# Sheet_2.net
KiCad netlist of a schematic drawn in EasyEDA
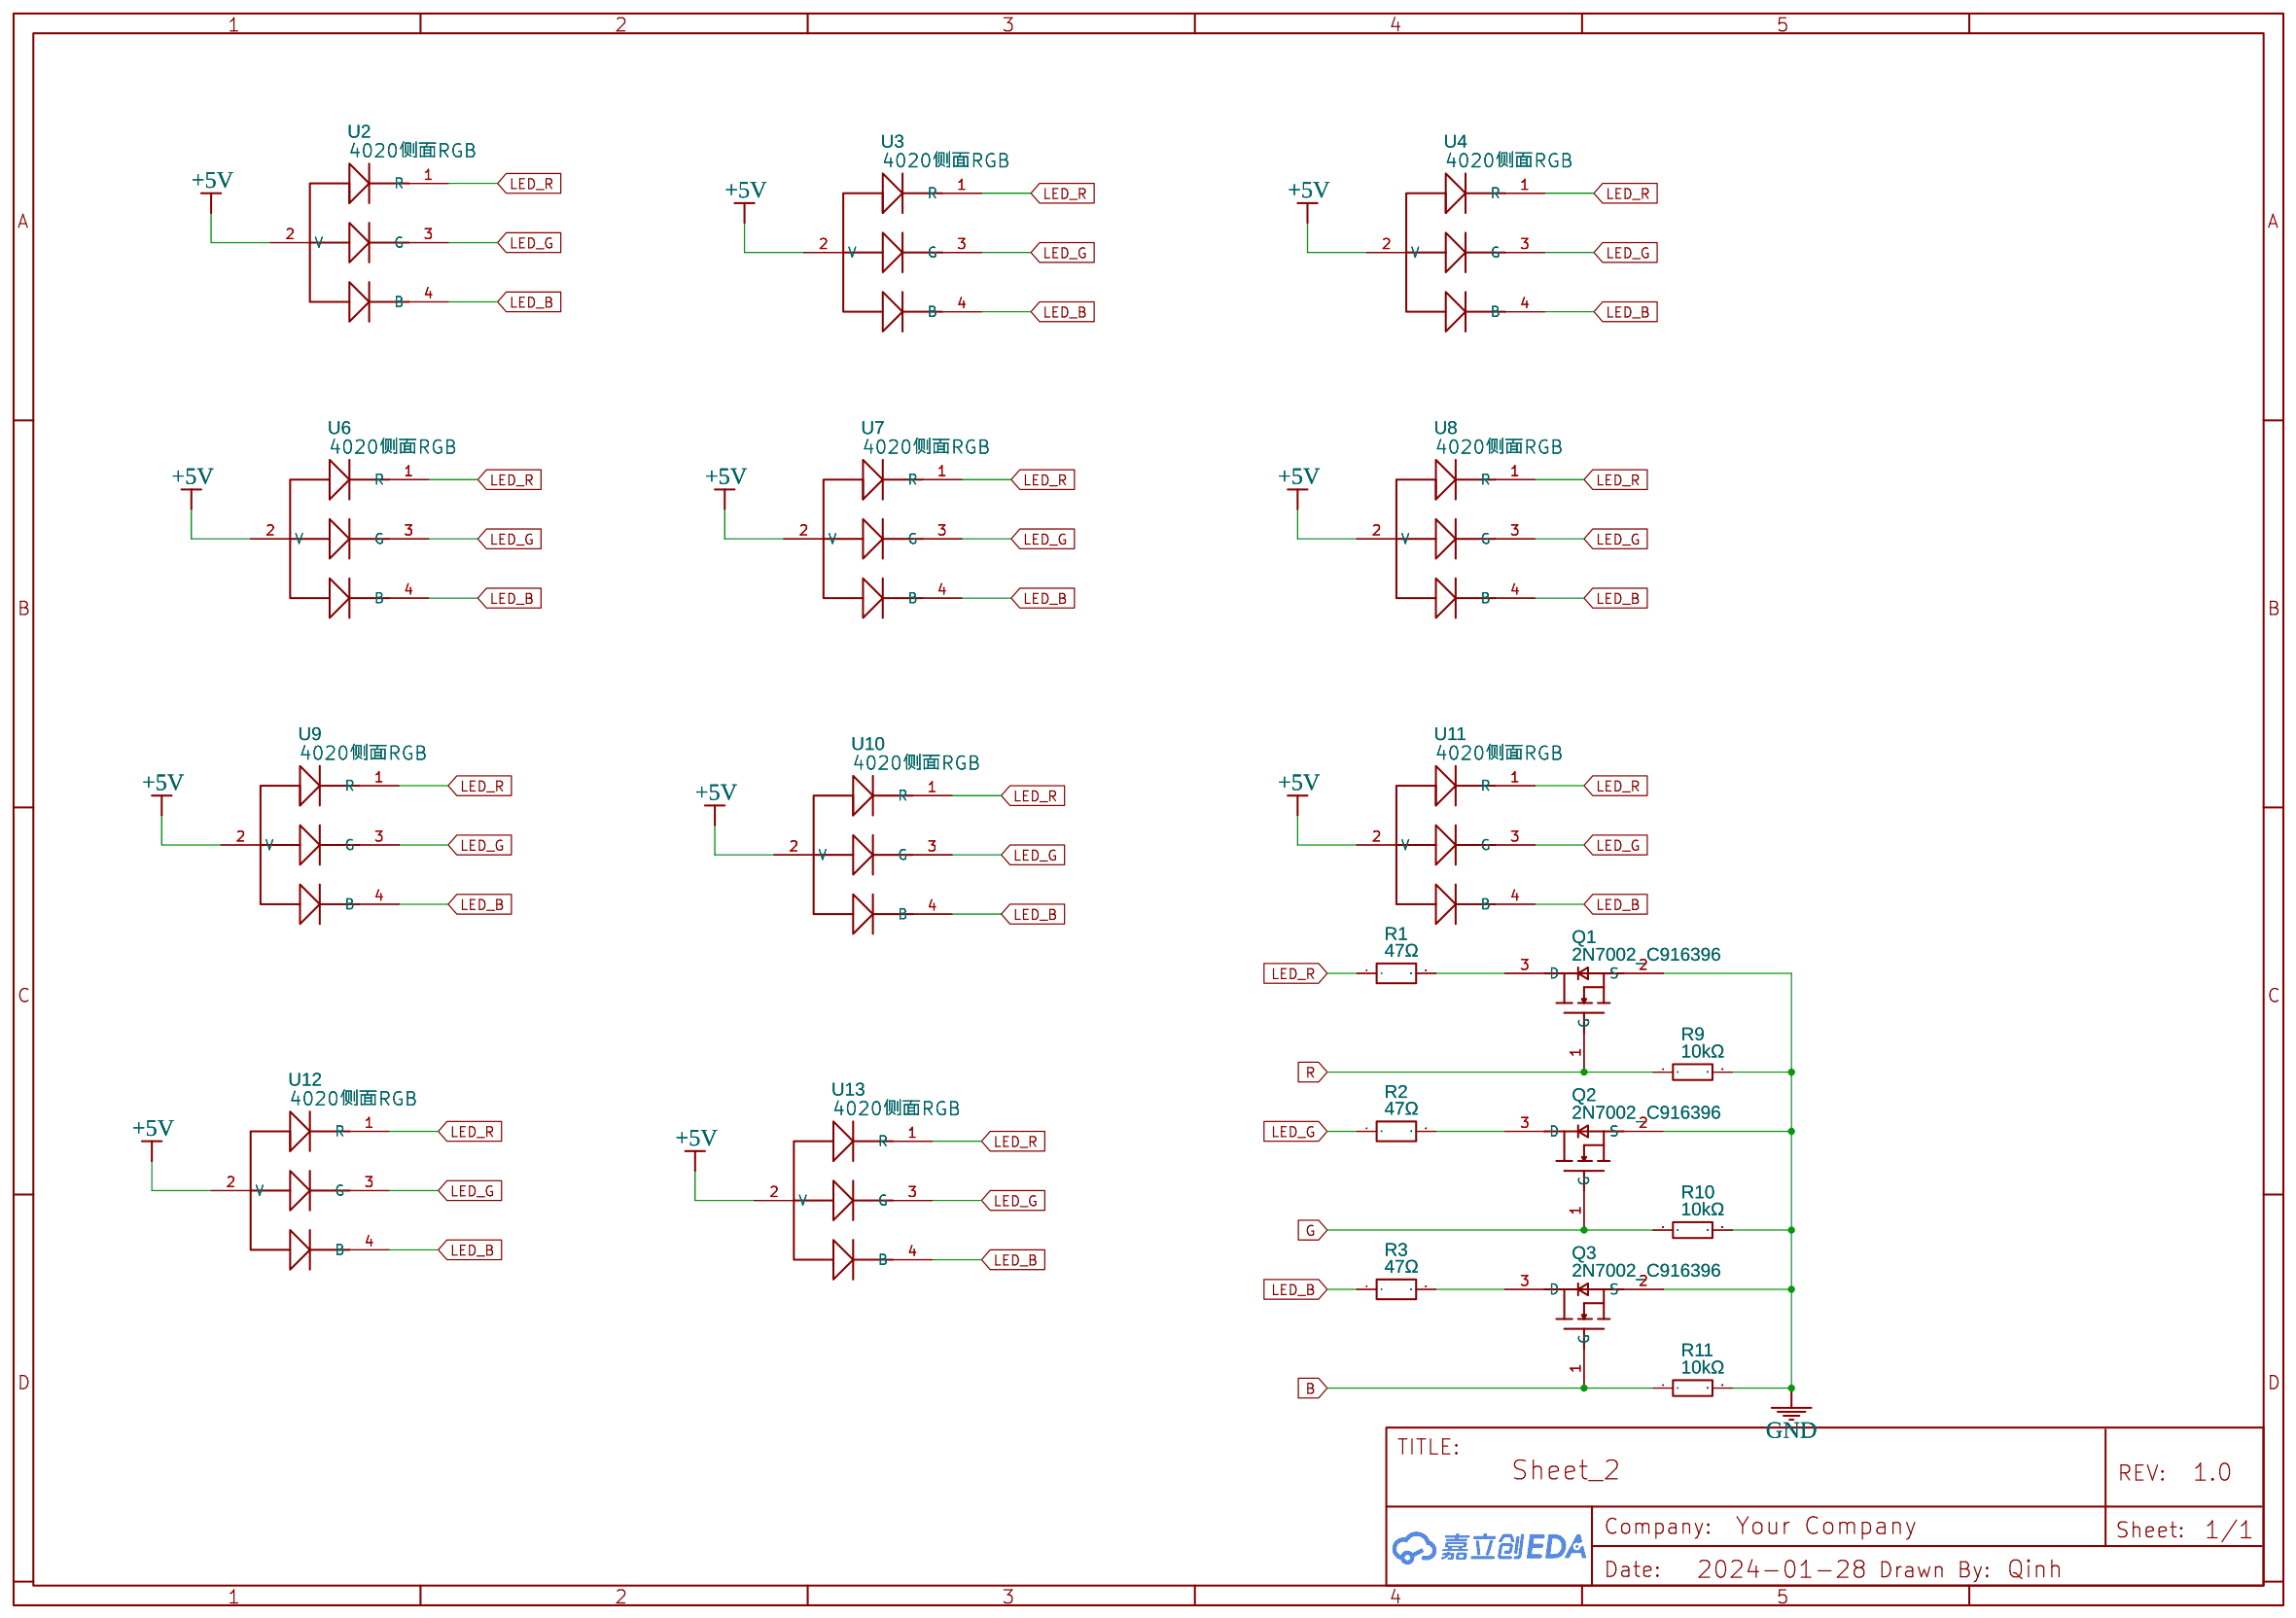
[diagram p0: schematic sheet]

(export (version "E")
  (design (tool "Eeschema 10.0.6"))
  (components
    (comp (ref "Q1")
      (value "2N7002_C916396")
      (fields (field (name "Manufacturer Part") "2N7002") (field (name "Manufacturer") "JSMSEMI(杰盛微)"))
      (libsource (lib "") (part "2N7002_C916396"))
    )
    (comp (ref "Q2")
      (value "2N7002_C916396")
      (fields (field (name "Manufacturer Part") "2N7002") (field (name "Manufacturer") "JSMSEMI(杰盛微)"))
      (libsource (lib "") (part "2N7002_C916396"))
    )
    (comp (ref "Q3")
      (value "2N7002_C916396")
      (fields (field (name "Manufacturer Part") "2N7002") (field (name "Manufacturer") "JSMSEMI(杰盛微)"))
      (libsource (lib "") (part "2N7002_C916396"))
    )
    (comp (ref "R1")
      (value "47Ω")
      (fields
        (field (name "Manufacturer Part") "CRCW060347R0FKEA")
        (field (name "Manufacturer") "VISHAY(威世)")
      )
      (libsource (lib "") (part "CRCW060347R0FKEA"))
    )
    (comp (ref "R2")
      (value "47Ω")
      (fields
        (field (name "Manufacturer Part") "CRCW060347R0FKEA")
        (field (name "Manufacturer") "VISHAY(威世)")
      )
      (libsource (lib "") (part "CRCW060347R0FKEA"))
    )
    (comp (ref "R3")
      (value "47Ω")
      (fields
        (field (name "Manufacturer Part") "CRCW060347R0FKEA")
        (field (name "Manufacturer") "VISHAY(威世)")
      )
      (libsource (lib "") (part "CRCW060347R0FKEA"))
    )
    (comp (ref "R9")
      (value "10kΩ")
      (fields
        (field (name "Manufacturer Part") "0603WAF1002T5E")
        (field (name "Manufacturer") "UNI-ROYAL(厚声)")
      )
      (libsource (lib "") (part "0603WAF1002T5E"))
    )
    (comp (ref "R10")
      (value "10kΩ")
      (fields
        (field (name "Manufacturer Part") "0603WAF1002T5E")
        (field (name "Manufacturer") "UNI-ROYAL(厚声)")
      )
      (libsource (lib "") (part "0603WAF1002T5E"))
    )
    (comp (ref "R11")
      (value "10kΩ")
      (fields
        (field (name "Manufacturer Part") "0603WAF1002T5E")
        (field (name "Manufacturer") "UNI-ROYAL(厚声)")
      )
      (libsource (lib "") (part "0603WAF1002T5E"))
    )
    (comp (ref "U2") (value "4020侧面RGB") (libsource (lib "") (part "4020侧面RGB")))
    (comp (ref "U3") (value "4020侧面RGB") (libsource (lib "") (part "4020侧面RGB")))
    (comp (ref "U4") (value "4020侧面RGB") (libsource (lib "") (part "4020侧面RGB")))
    (comp (ref "U6") (value "4020侧面RGB") (libsource (lib "") (part "4020侧面RGB")))
    (comp (ref "U7") (value "4020侧面RGB") (libsource (lib "") (part "4020侧面RGB")))
    (comp (ref "U8") (value "4020侧面RGB") (libsource (lib "") (part "4020侧面RGB")))
    (comp (ref "U9") (value "4020侧面RGB") (libsource (lib "") (part "4020侧面RGB")))
    (comp (ref "U10") (value "4020侧面RGB") (libsource (lib "") (part "4020侧面RGB")))
    (comp (ref "U11") (value "4020侧面RGB") (libsource (lib "") (part "4020侧面RGB")))
    (comp (ref "U12") (value "4020侧面RGB") (libsource (lib "") (part "4020侧面RGB")))
    (comp (ref "U13") (value "4020侧面RGB") (libsource (lib "") (part "4020侧面RGB")))
  )
  (nets
    (net (code "1") (name "+5V") (class "Default")
      (node (ref "U10") (pin "2") (pinfunction "V_2") (pintype "unspecified"))
      (node (ref "U11") (pin "2") (pinfunction "V_2") (pintype "unspecified"))
      (node (ref "U12") (pin "2") (pinfunction "V_2") (pintype "unspecified"))
      (node (ref "U13") (pin "2") (pinfunction "V_2") (pintype "unspecified"))
      (node (ref "U2") (pin "2") (pinfunction "V_2") (pintype "unspecified"))
      (node (ref "U3") (pin "2") (pinfunction "V_2") (pintype "unspecified"))
      (node (ref "U4") (pin "2") (pinfunction "V_2") (pintype "unspecified"))
      (node (ref "U6") (pin "2") (pinfunction "V_2") (pintype "unspecified"))
      (node (ref "U7") (pin "2") (pinfunction "V_2") (pintype "unspecified"))
      (node (ref "U8") (pin "2") (pinfunction "V_2") (pintype "unspecified"))
      (node (ref "U9") (pin "2") (pinfunction "V_2") (pintype "unspecified"))
    )
    (net (code "2") (name "B") (class "Default")
      (node (ref "Q3") (pin "1") (pinfunction "G_1") (pintype "unspecified"))
      (node (ref "R11") (pin "1") (pinfunction "1_1") (pintype "input"))
    )
    (net (code "3") (name "G") (class "Default")
      (node (ref "Q2") (pin "1") (pinfunction "G_1") (pintype "unspecified"))
      (node (ref "R10") (pin "1") (pinfunction "1_1") (pintype "input"))
    )
    (net (code "4") (name "GND") (class "Default")
      (node (ref "Q1") (pin "2") (pinfunction "S_2") (pintype "unspecified"))
      (node (ref "Q2") (pin "2") (pinfunction "S_2") (pintype "unspecified"))
      (node (ref "Q3") (pin "2") (pinfunction "S_2") (pintype "unspecified"))
      (node (ref "R10") (pin "2") (pinfunction "2_2") (pintype "input"))
      (node (ref "R11") (pin "2") (pinfunction "2_2") (pintype "input"))
      (node (ref "R9") (pin "2") (pinfunction "2_2") (pintype "input"))
    )
    (net (code "5") (name "LED_B") (class "Default")
      (node (ref "R3") (pin "1") (pinfunction "1_1") (pintype "unspecified"))
      (node (ref "U10") (pin "4") (pinfunction "B_4") (pintype "unspecified"))
      (node (ref "U11") (pin "4") (pinfunction "B_4") (pintype "unspecified"))
      (node (ref "U12") (pin "4") (pinfunction "B_4") (pintype "unspecified"))
      (node (ref "U13") (pin "4") (pinfunction "B_4") (pintype "unspecified"))
      (node (ref "U2") (pin "4") (pinfunction "B_4") (pintype "unspecified"))
      (node (ref "U3") (pin "4") (pinfunction "B_4") (pintype "unspecified"))
      (node (ref "U4") (pin "4") (pinfunction "B_4") (pintype "unspecified"))
      (node (ref "U6") (pin "4") (pinfunction "B_4") (pintype "unspecified"))
      (node (ref "U7") (pin "4") (pinfunction "B_4") (pintype "unspecified"))
      (node (ref "U8") (pin "4") (pinfunction "B_4") (pintype "unspecified"))
      (node (ref "U9") (pin "4") (pinfunction "B_4") (pintype "unspecified"))
    )
    (net (code "6") (name "LED_G") (class "Default")
      (node (ref "R2") (pin "1") (pinfunction "1_1") (pintype "unspecified"))
      (node (ref "U10") (pin "3") (pinfunction "G_3") (pintype "unspecified"))
      (node (ref "U11") (pin "3") (pinfunction "G_3") (pintype "unspecified"))
      (node (ref "U12") (pin "3") (pinfunction "G_3") (pintype "unspecified"))
      (node (ref "U13") (pin "3") (pinfunction "G_3") (pintype "unspecified"))
      (node (ref "U2") (pin "3") (pinfunction "G_3") (pintype "unspecified"))
      (node (ref "U3") (pin "3") (pinfunction "G_3") (pintype "unspecified"))
      (node (ref "U4") (pin "3") (pinfunction "G_3") (pintype "unspecified"))
      (node (ref "U6") (pin "3") (pinfunction "G_3") (pintype "unspecified"))
      (node (ref "U7") (pin "3") (pinfunction "G_3") (pintype "unspecified"))
      (node (ref "U8") (pin "3") (pinfunction "G_3") (pintype "unspecified"))
      (node (ref "U9") (pin "3") (pinfunction "G_3") (pintype "unspecified"))
    )
    (net (code "7") (name "LED_R") (class "Default")
      (node (ref "R1") (pin "1") (pinfunction "1_1") (pintype "unspecified"))
      (node (ref "U10") (pin "1") (pinfunction "R_1") (pintype "unspecified"))
      (node (ref "U11") (pin "1") (pinfunction "R_1") (pintype "unspecified"))
      (node (ref "U12") (pin "1") (pinfunction "R_1") (pintype "unspecified"))
      (node (ref "U13") (pin "1") (pinfunction "R_1") (pintype "unspecified"))
      (node (ref "U2") (pin "1") (pinfunction "R_1") (pintype "unspecified"))
      (node (ref "U3") (pin "1") (pinfunction "R_1") (pintype "unspecified"))
      (node (ref "U4") (pin "1") (pinfunction "R_1") (pintype "unspecified"))
      (node (ref "U6") (pin "1") (pinfunction "R_1") (pintype "unspecified"))
      (node (ref "U7") (pin "1") (pinfunction "R_1") (pintype "unspecified"))
      (node (ref "U8") (pin "1") (pinfunction "R_1") (pintype "unspecified"))
      (node (ref "U9") (pin "1") (pinfunction "R_1") (pintype "unspecified"))
    )
    (net (code "8") (name "Net-(Q1-D)") (class "Default")
      (node (ref "Q1") (pin "3") (pinfunction "D_3") (pintype "unspecified"))
      (node (ref "R1") (pin "2") (pinfunction "2_2") (pintype "unspecified"))
    )
    (net (code "9") (name "Net-(Q2-D)") (class "Default")
      (node (ref "Q2") (pin "3") (pinfunction "D_3") (pintype "unspecified"))
      (node (ref "R2") (pin "2") (pinfunction "2_2") (pintype "unspecified"))
    )
    (net (code "10") (name "Net-(Q3-D)") (class "Default")
      (node (ref "Q3") (pin "3") (pinfunction "D_3") (pintype "unspecified"))
      (node (ref "R3") (pin "2") (pinfunction "2_2") (pintype "unspecified"))
    )
    (net (code "11") (name "R") (class "Default")
      (node (ref "Q1") (pin "1") (pinfunction "G_1") (pintype "unspecified"))
      (node (ref "R9") (pin "1") (pinfunction "1_1") (pintype "input"))
    )
  )
)
